# Circuito_Tappingduino_3_Final.net
KiCad netlist of a schematic drawn in EAGLE
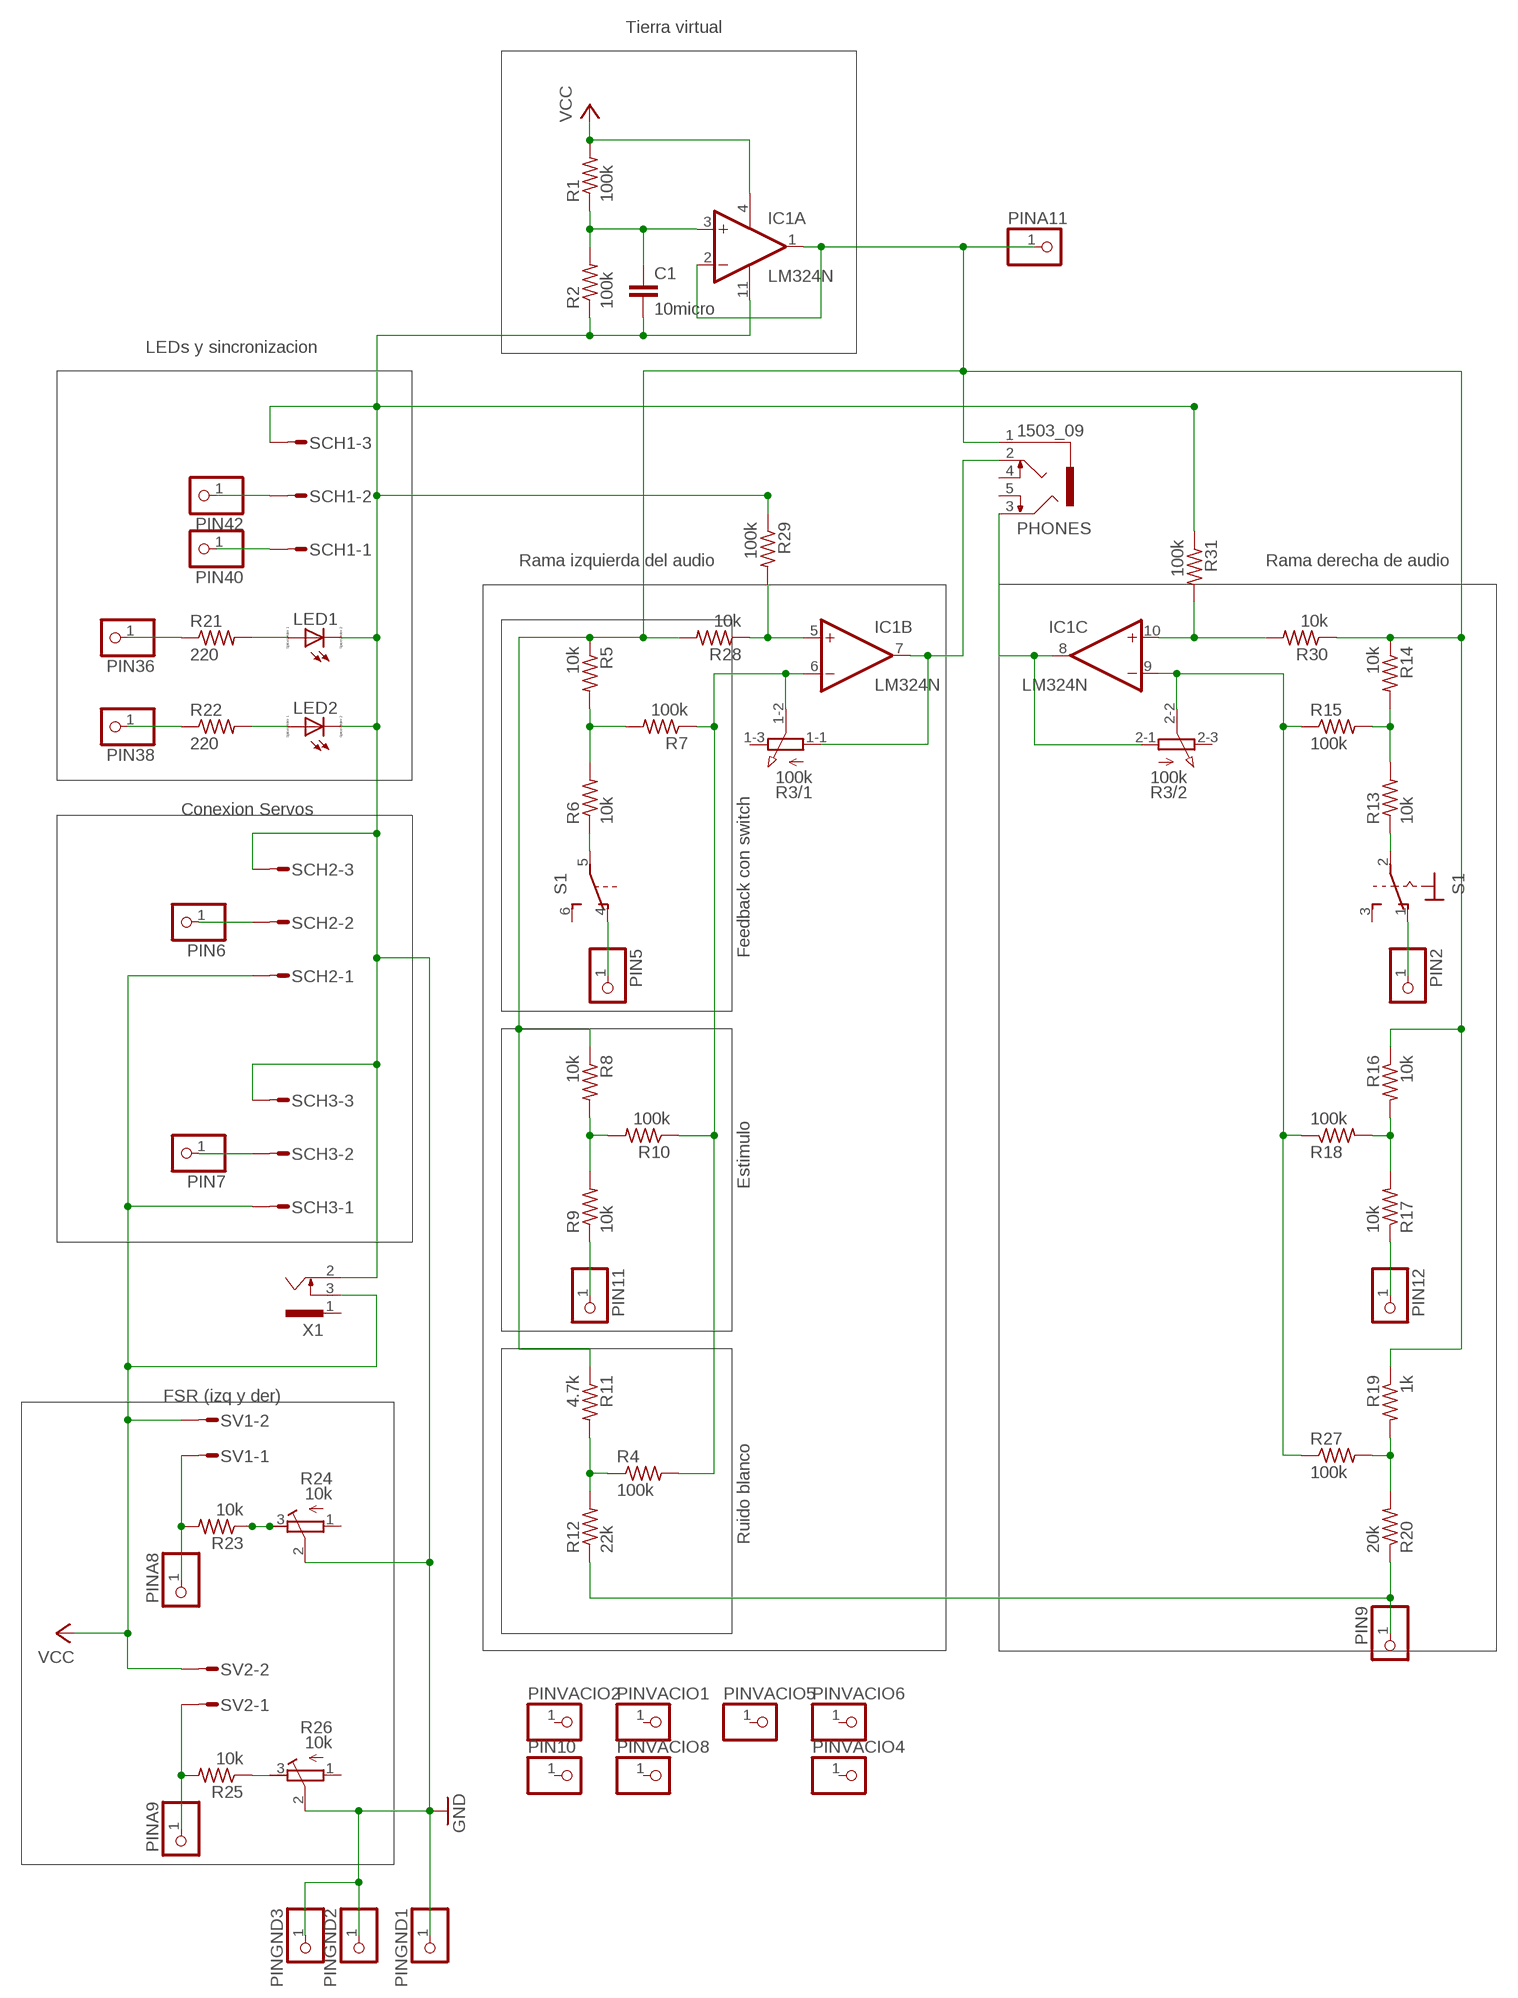
[diagram p0: schematic, sheet 1]

(export (version "E")
  (design (tool "Eeschema 10.0.6"))
  (components
    (comp (ref "C1")
      (value "10micro")
      (footprint "eagle-import:C025-030X050")
      (libsource (lib "eagle-import") (part "C-EU025-030X050"))
    )
    (comp (ref "IC1")
      (value "LM324N")
      (footprint "eagle-import:DIL14")
      (fields (field (name "SPICEPREFIX") "X"))
      (libsource (lib "eagle-import") (part "LM324N"))
    )
    (comp (ref "LED1")
      (value "LED_ELD260")
      (footprint "eagle-import:LED_LD260")
      (fields (field (name "SPICEMODEL") "DMOD"))
      (libsource (lib "eagle-import") (part "LED_ELD260"))
    )
    (comp (ref "LED2")
      (value "LED_ELD260")
      (footprint "eagle-import:LED_LD260")
      (fields (field (name "SPICEMODEL") "DMOD"))
      (libsource (lib "eagle-import") (part "LED_ELD260"))
    )
    (comp (ref "PHONES")
      (value "1503_09")
      (footprint "eagle-import:1503_09")
      (fields (field (name "SPICEPREFIX") "X"))
      (libsource (lib "eagle-import") (part "1503_09"))
    )
    (comp (ref "PIN2")
      (value "PINHD-1X1")
      (footprint "eagle-import:1X01")
      (fields (field (name "SPICEPREFIX") "X"))
      (libsource (lib "eagle-import") (part "PINHD-1X1"))
    )
    (comp (ref "PIN5")
      (value "PINHD-1X1")
      (footprint "eagle-import:1X01")
      (fields (field (name "SPICEPREFIX") "X"))
      (libsource (lib "eagle-import") (part "PINHD-1X1"))
    )
    (comp (ref "PIN6")
      (value "PINHD-1X1")
      (footprint "eagle-import:1X01")
      (fields (field (name "SPICEPREFIX") "X"))
      (libsource (lib "eagle-import") (part "PINHD-1X1"))
    )
    (comp (ref "PIN7")
      (value "PINHD-1X1")
      (footprint "eagle-import:1X01")
      (fields (field (name "SPICEPREFIX") "X"))
      (libsource (lib "eagle-import") (part "PINHD-1X1"))
    )
    (comp (ref "PIN9")
      (value "PINHD-1X1")
      (footprint "eagle-import:1X01")
      (fields (field (name "SPICEPREFIX") "X"))
      (libsource (lib "eagle-import") (part "PINHD-1X1"))
    )
    (comp (ref "PIN10")
      (value "PINHD-1X1")
      (footprint "eagle-import:1X01")
      (fields (field (name "SPICEPREFIX") "X"))
      (libsource (lib "eagle-import") (part "PINHD-1X1"))
    )
    (comp (ref "PIN11")
      (value "PINHD-1X1")
      (footprint "eagle-import:1X01")
      (fields (field (name "SPICEPREFIX") "X"))
      (libsource (lib "eagle-import") (part "PINHD-1X1"))
    )
    (comp (ref "PIN12")
      (value "PINHD-1X1")
      (footprint "eagle-import:1X01")
      (fields (field (name "SPICEPREFIX") "X"))
      (libsource (lib "eagle-import") (part "PINHD-1X1"))
    )
    (comp (ref "PIN36")
      (value "PINHD-1X1")
      (footprint "eagle-import:1X01")
      (fields (field (name "SPICEPREFIX") "X"))
      (libsource (lib "eagle-import") (part "PINHD-1X1"))
    )
    (comp (ref "PIN38")
      (value "PINHD-1X1")
      (footprint "eagle-import:1X01")
      (fields (field (name "SPICEPREFIX") "X"))
      (libsource (lib "eagle-import") (part "PINHD-1X1"))
    )
    (comp (ref "PIN40")
      (value "PINHD-1X1")
      (footprint "eagle-import:1X01")
      (fields (field (name "SPICEPREFIX") "X"))
      (libsource (lib "eagle-import") (part "PINHD-1X1"))
    )
    (comp (ref "PIN42")
      (value "PINHD-1X1")
      (footprint "eagle-import:1X01")
      (fields (field (name "SPICEPREFIX") "X"))
      (libsource (lib "eagle-import") (part "PINHD-1X1"))
    )
    (comp (ref "PINA8")
      (value "PINHD-1X1")
      (footprint "eagle-import:1X01")
      (fields (field (name "SPICEPREFIX") "X"))
      (libsource (lib "eagle-import") (part "PINHD-1X1"))
    )
    (comp (ref "PINA9")
      (value "PINHD-1X1")
      (footprint "eagle-import:1X01")
      (fields (field (name "SPICEPREFIX") "X"))
      (libsource (lib "eagle-import") (part "PINHD-1X1"))
    )
    (comp (ref "PINA11")
      (value "PINHD-1X1")
      (footprint "eagle-import:1X01")
      (fields (field (name "SPICEPREFIX") "X"))
      (libsource (lib "eagle-import") (part "PINHD-1X1"))
    )
    (comp (ref "PINGND1")
      (value "PINHD-1X1")
      (footprint "eagle-import:1X01")
      (fields (field (name "SPICEPREFIX") "X"))
      (libsource (lib "eagle-import") (part "PINHD-1X1"))
    )
    (comp (ref "PINGND2")
      (value "PINHD-1X1")
      (footprint "eagle-import:1X01")
      (fields (field (name "SPICEPREFIX") "X"))
      (libsource (lib "eagle-import") (part "PINHD-1X1"))
    )
    (comp (ref "PINGND3")
      (value "PINHD-1X1")
      (footprint "eagle-import:1X01")
      (fields (field (name "SPICEPREFIX") "X"))
      (libsource (lib "eagle-import") (part "PINHD-1X1"))
    )
    (comp (ref "PINVACIO1")
      (value "PINHD-1X1")
      (footprint "eagle-import:1X01")
      (fields (field (name "SPICEPREFIX") "X"))
      (libsource (lib "eagle-import") (part "PINHD-1X1"))
    )
    (comp (ref "PINVACIO2")
      (value "PINHD-1X1")
      (footprint "eagle-import:1X01")
      (fields (field (name "SPICEPREFIX") "X"))
      (libsource (lib "eagle-import") (part "PINHD-1X1"))
    )
    (comp (ref "PINVACIO4")
      (value "PINHD-1X1")
      (footprint "eagle-import:1X01")
      (fields (field (name "SPICEPREFIX") "X"))
      (libsource (lib "eagle-import") (part "PINHD-1X1"))
    )
    (comp (ref "PINVACIO5")
      (value "PINHD-1X1")
      (footprint "eagle-import:1X01")
      (fields (field (name "SPICEPREFIX") "X"))
      (libsource (lib "eagle-import") (part "PINHD-1X1"))
    )
    (comp (ref "PINVACIO6")
      (value "PINHD-1X1")
      (footprint "eagle-import:1X01")
      (fields (field (name "SPICEPREFIX") "X"))
      (libsource (lib "eagle-import") (part "PINHD-1X1"))
    )
    (comp (ref "PINVACIO8")
      (value "PINHD-1X1")
      (footprint "eagle-import:1X01")
      (fields (field (name "SPICEPREFIX") "X"))
      (libsource (lib "eagle-import") (part "PINHD-1X1"))
    )
    (comp (ref "R1")
      (value "100k")
      (footprint "eagle-import:0207_7")
      (libsource (lib "eagle-import") (part "R-US_0207/7"))
    )
    (comp (ref "R2")
      (value "100k")
      (footprint "eagle-import:0207_7")
      (libsource (lib "eagle-import") (part "R-US_0207/7"))
    )
    (comp (ref "R3")
      (value "100k")
      (footprint "eagle-import:3RP_1610G")
      (fields (field (name "SPICEPREFIX") "J"))
      (libsource (lib "eagle-import") (part "3RP/1610G"))
    )
    (comp (ref "R4")
      (value "100k")
      (footprint "eagle-import:0207_7")
      (libsource (lib "eagle-import") (part "R-US_0207/7"))
    )
    (comp (ref "R5")
      (value "10k")
      (footprint "eagle-import:0207_7")
      (libsource (lib "eagle-import") (part "R-US_0207/7"))
    )
    (comp (ref "R6")
      (value "10k")
      (footprint "eagle-import:0207_7")
      (libsource (lib "eagle-import") (part "R-US_0207/7"))
    )
    (comp (ref "R7")
      (value "100k")
      (footprint "eagle-import:0207_7")
      (libsource (lib "eagle-import") (part "R-US_0207/7"))
    )
    (comp (ref "R8")
      (value "10k")
      (footprint "eagle-import:0207_7")
      (libsource (lib "eagle-import") (part "R-US_0207/7"))
    )
    (comp (ref "R9")
      (value "10k")
      (footprint "eagle-import:0207_7")
      (libsource (lib "eagle-import") (part "R-US_0207/7"))
    )
    (comp (ref "R10")
      (value "100k")
      (footprint "eagle-import:0207_7")
      (libsource (lib "eagle-import") (part "R-US_0207/7"))
    )
    (comp (ref "R11")
      (value "4.7k")
      (footprint "eagle-import:0207_7")
      (libsource (lib "eagle-import") (part "R-US_0207/7"))
    )
    (comp (ref "R12")
      (value "22k")
      (footprint "eagle-import:0207_7")
      (libsource (lib "eagle-import") (part "R-US_0207/7"))
    )
    (comp (ref "R13")
      (value "10k")
      (footprint "eagle-import:0207_7")
      (libsource (lib "eagle-import") (part "R-US_0207/7"))
    )
    (comp (ref "R14")
      (value "10k")
      (footprint "eagle-import:0207_7")
      (libsource (lib "eagle-import") (part "R-US_0207/7"))
    )
    (comp (ref "R15")
      (value "100k")
      (footprint "eagle-import:0207_7")
      (libsource (lib "eagle-import") (part "R-US_0207/7"))
    )
    (comp (ref "R16")
      (value "10k")
      (footprint "eagle-import:0207_7")
      (libsource (lib "eagle-import") (part "R-US_0207/7"))
    )
    (comp (ref "R17")
      (value "10k")
      (footprint "eagle-import:0207_7")
      (libsource (lib "eagle-import") (part "R-US_0207/7"))
    )
    (comp (ref "R18")
      (value "100k")
      (footprint "eagle-import:0207_7")
      (libsource (lib "eagle-import") (part "R-US_0207/7"))
    )
    (comp (ref "R19")
      (value "1k")
      (footprint "eagle-import:0207_7")
      (libsource (lib "eagle-import") (part "R-US_0207/7"))
    )
    (comp (ref "R20")
      (value "20k")
      (footprint "eagle-import:0207_7")
      (libsource (lib "eagle-import") (part "R-US_0207/7"))
    )
    (comp (ref "R21")
      (value "220")
      (footprint "eagle-import:0207_7")
      (libsource (lib "eagle-import") (part "R-US_0207/7"))
    )
    (comp (ref "R22")
      (value "220")
      (footprint "eagle-import:0207_7")
      (libsource (lib "eagle-import") (part "R-US_0207/7"))
    )
    (comp (ref "R23")
      (value "10k")
      (footprint "eagle-import:0207_7")
      (libsource (lib "eagle-import") (part "R-US_0207/7"))
    )
    (comp (ref "R24")
      (value "10k")
      (footprint "eagle-import:RTRIM64W")
      (libsource (lib "eagle-import") (part "R-TRIMM64W"))
    )
    (comp (ref "R25")
      (value "10k")
      (footprint "eagle-import:0207_7")
      (libsource (lib "eagle-import") (part "R-US_0207/7"))
    )
    (comp (ref "R26")
      (value "10k")
      (footprint "eagle-import:RTRIM64W")
      (libsource (lib "eagle-import") (part "R-TRIMM64W"))
    )
    (comp (ref "R27")
      (value "100k")
      (footprint "eagle-import:0207_7")
      (libsource (lib "eagle-import") (part "R-US_0207/7"))
    )
    (comp (ref "R28")
      (value "10k")
      (footprint "eagle-import:0207_7")
      (libsource (lib "eagle-import") (part "R-US_0207/7"))
    )
    (comp (ref "R29")
      (value "100k")
      (footprint "eagle-import:0207_7")
      (libsource (lib "eagle-import") (part "R-US_0207/7"))
    )
    (comp (ref "R30")
      (value "10k")
      (footprint "eagle-import:0207_7")
      (libsource (lib "eagle-import") (part "R-US_0207/7"))
    )
    (comp (ref "R31")
      (value "100k")
      (footprint "eagle-import:0207_7")
      (libsource (lib "eagle-import") (part "R-US_0207/7"))
    )
    (comp (ref "S1")
      (value "320-938")
      (footprint "eagle-import:320-938")
      (libsource (lib "eagle-import") (part "320-938"))
    )
    (comp (ref "SCH1")
      (value "L03P")
      (footprint "eagle-import:L03P")
      (fields (field (name "SPICEPREFIX") "X"))
      (libsource (lib "eagle-import") (part "L03P"))
    )
    (comp (ref "SCH2")
      (value "L03P")
      (footprint "eagle-import:L03P")
      (fields (field (name "SPICEPREFIX") "X"))
      (libsource (lib "eagle-import") (part "L03P"))
    )
    (comp (ref "SCH3")
      (value "L03P")
      (footprint "eagle-import:L03P")
      (fields (field (name "SPICEPREFIX") "X"))
      (libsource (lib "eagle-import") (part "L03P"))
    )
    (comp (ref "SV1")
      (value "L02P")
      (footprint "eagle-import:L02P")
      (fields (field (name "SPICEPREFIX") "X"))
      (libsource (lib "eagle-import") (part "L02P"))
    )
    (comp (ref "SV2")
      (value "L02P")
      (footprint "eagle-import:L02P")
      (fields (field (name "SPICEPREFIX") "X"))
      (libsource (lib "eagle-import") (part "L02P"))
    )
    (comp (ref "X1")
      (value "SCD-014A")
      (footprint "eagle-import:SCD-014-A")
      (fields (field (name "SPICEPREFIX") "X"))
      (libsource (lib "eagle-import") (part "SCD-014A"))
    )
  )
  (nets
    (net (code "1") (name "GND") (class "Default")
      (node (ref "C1") (pin "2") (pinfunction "2_2") (pintype "passive"))
      (node (ref "IC1") (pin "11") (pinfunction "V-_11") (pintype "power_in"))
      (node (ref "LED1") (pin "K") (pinfunction "C_K") (pintype "passive"))
      (node (ref "LED2") (pin "K") (pinfunction "C_K") (pintype "passive"))
      (node (ref "PINGND1") (pin "1") (pinfunction "1_1") (pintype "passive"))
      (node (ref "PINGND2") (pin "1") (pinfunction "1_1") (pintype "passive"))
      (node (ref "PINGND3") (pin "1") (pinfunction "1_1") (pintype "passive"))
      (node (ref "R2") (pin "1") (pinfunction "1_1") (pintype "passive"))
      (node (ref "R24") (pin "2") (pinfunction "S_2") (pintype "passive"))
      (node (ref "R26") (pin "2") (pinfunction "S_2") (pintype "passive"))
      (node (ref "R29") (pin "1") (pinfunction "1_1") (pintype "passive"))
      (node (ref "R31") (pin "1") (pinfunction "1_1") (pintype "passive"))
      (node (ref "SCH1") (pin "3") (pinfunction "S_3") (pintype "passive"))
      (node (ref "SCH2") (pin "3") (pinfunction "S_3") (pintype "passive"))
      (node (ref "SCH3") (pin "3") (pinfunction "S_3") (pintype "passive"))
      (node (ref "X1") (pin "2") (pinfunction "2_2") (pintype "passive"))
    )
    (net (code "2") (name "Net-(IC1A-+IN)") (class "Default")
      (node (ref "C1") (pin "1") (pinfunction "1_1") (pintype "passive"))
      (node (ref "IC1") (pin "3") (pinfunction "+IN_3") (pintype "input"))
      (node (ref "R1") (pin "1") (pinfunction "1_1") (pintype "passive"))
      (node (ref "R2") (pin "2") (pinfunction "2_2") (pintype "passive"))
    )
    (net (code "3") (name "Net-(IC1A--IN)") (class "Default")
      (node (ref "IC1") (pin "1") (pinfunction "OUT_1") (pintype "output"))
      (node (ref "IC1") (pin "2") (pinfunction "-IN_2") (pintype "input"))
      (node (ref "PHONES") (pin "1") (pinfunction "1_1") (pintype "passive"))
      (node (ref "PINA11") (pin "1") (pinfunction "1_1") (pintype "passive"))
      (node (ref "R11") (pin "1") (pinfunction "1_1") (pintype "passive"))
      (node (ref "R14") (pin "1") (pinfunction "1_1") (pintype "passive"))
      (node (ref "R16") (pin "1") (pinfunction "1_1") (pintype "passive"))
      (node (ref "R19") (pin "1") (pinfunction "1_1") (pintype "passive"))
      (node (ref "R28") (pin "2") (pinfunction "2_2") (pintype "passive"))
      (node (ref "R30") (pin "1") (pinfunction "1_1") (pintype "passive"))
      (node (ref "R5") (pin "1") (pinfunction "1_1") (pintype "passive"))
      (node (ref "R8") (pin "1") (pinfunction "1_1") (pintype "passive"))
    )
    (net (code "4") (name "Net-(IC1B-+IN)") (class "Default")
      (node (ref "IC1") (pin "5") (pinfunction "+IN_5") (pintype "input"))
      (node (ref "R28") (pin "1") (pinfunction "1_1") (pintype "passive"))
      (node (ref "R29") (pin "2") (pinfunction "2_2") (pintype "passive"))
    )
    (net (code "5") (name "Net-(IC1B--IN)") (class "Default")
      (node (ref "IC1") (pin "6") (pinfunction "-IN_6") (pintype "input"))
      (node (ref "R10") (pin "1") (pinfunction "1_1") (pintype "passive"))
      (node (ref "R3") (pin "1-2") (pinfunction "S_1-2") (pintype "passive"))
      (node (ref "R4") (pin "2") (pinfunction "2_2") (pintype "passive"))
      (node (ref "R7") (pin "1") (pinfunction "1_1") (pintype "passive"))
    )
    (net (code "6") (name "Net-(IC1B-OUT)") (class "Default")
      (node (ref "IC1") (pin "7") (pinfunction "OUT_7") (pintype "output"))
      (node (ref "PHONES") (pin "2") (pinfunction "2_2") (pintype "passive"))
      (node (ref "R3") (pin "1-1") (pinfunction "A_1-1") (pintype "passive"))
    )
    (net (code "7") (name "Net-(IC1C-+IN)") (class "Default")
      (node (ref "IC1") (pin "10") (pinfunction "+IN_10") (pintype "input"))
      (node (ref "R30") (pin "2") (pinfunction "2_2") (pintype "passive"))
      (node (ref "R31") (pin "2") (pinfunction "2_2") (pintype "passive"))
    )
    (net (code "8") (name "Net-(IC1C--IN)") (class "Default")
      (node (ref "IC1") (pin "9") (pinfunction "-IN_9") (pintype "input"))
      (node (ref "R15") (pin "1") (pinfunction "1_1") (pintype "passive"))
      (node (ref "R18") (pin "1") (pinfunction "1_1") (pintype "passive"))
      (node (ref "R27") (pin "1") (pinfunction "1_1") (pintype "passive"))
      (node (ref "R3") (pin "2-2") (pinfunction "S_2-2") (pintype "passive"))
    )
    (net (code "9") (name "Net-(IC1C-OUT)") (class "Default")
      (node (ref "IC1") (pin "8") (pinfunction "OUT_8") (pintype "output"))
      (node (ref "PHONES") (pin "3") (pinfunction "3_3") (pintype "passive"))
      (node (ref "R3") (pin "2-1") (pinfunction "A_2-1") (pintype "passive"))
    )
    (net (code "10") (name "Net-(LED1-PadA)") (class "Default")
      (node (ref "LED1") (pin "A") (pinfunction "A_A") (pintype "passive"))
      (node (ref "R21") (pin "2") (pinfunction "2_2") (pintype "passive"))
    )
    (net (code "11") (name "Net-(LED2-PadA)") (class "Default")
      (node (ref "LED2") (pin "A") (pinfunction "A_A") (pintype "passive"))
      (node (ref "R22") (pin "2") (pinfunction "2_2") (pintype "passive"))
    )
    (net (code "12") (name "Net-(PIN9-Pad1)") (class "Default")
      (node (ref "PIN9") (pin "1") (pinfunction "1_1") (pintype "passive"))
      (node (ref "R12") (pin "1") (pinfunction "1_1") (pintype "passive"))
      (node (ref "R20") (pin "1") (pinfunction "1_1") (pintype "passive"))
    )
    (net (code "13") (name "Net-(PIN11-Pad1)") (class "Default")
      (node (ref "PIN11") (pin "1") (pinfunction "1_1") (pintype "passive"))
      (node (ref "R9") (pin "1") (pinfunction "1_1") (pintype "passive"))
    )
    (net (code "14") (name "Net-(PIN12-Pad1)") (class "Default")
      (node (ref "PIN12") (pin "1") (pinfunction "1_1") (pintype "passive"))
      (node (ref "R17") (pin "1") (pinfunction "1_1") (pintype "passive"))
    )
    (net (code "15") (name "Net-(PIN36-Pad1)") (class "Default")
      (node (ref "PIN36") (pin "1") (pinfunction "1_1") (pintype "passive"))
      (node (ref "R21") (pin "1") (pinfunction "1_1") (pintype "passive"))
    )
    (net (code "16") (name "Net-(PIN38-Pad1)") (class "Default")
      (node (ref "PIN38") (pin "1") (pinfunction "1_1") (pintype "passive"))
      (node (ref "R22") (pin "1") (pinfunction "1_1") (pintype "passive"))
    )
    (net (code "17") (name "Net-(R5-Pad2)") (class "Default")
      (node (ref "R5") (pin "2") (pinfunction "2_2") (pintype "passive"))
      (node (ref "R6") (pin "2") (pinfunction "2_2") (pintype "passive"))
      (node (ref "R7") (pin "2") (pinfunction "2_2") (pintype "passive"))
    )
    (net (code "18") (name "Net-(R10-Pad2)") (class "Default")
      (node (ref "R10") (pin "2") (pinfunction "2_2") (pintype "passive"))
      (node (ref "R8") (pin "2") (pinfunction "2_2") (pintype "passive"))
      (node (ref "R9") (pin "2") (pinfunction "2_2") (pintype "passive"))
    )
    (net (code "19") (name "Net-(R11-Pad2)") (class "Default")
      (node (ref "R11") (pin "2") (pinfunction "2_2") (pintype "passive"))
      (node (ref "R12") (pin "2") (pinfunction "2_2") (pintype "passive"))
      (node (ref "R4") (pin "1") (pinfunction "1_1") (pintype "passive"))
    )
    (net (code "20") (name "Net-(R13-Pad2)") (class "Default")
      (node (ref "R13") (pin "2") (pinfunction "2_2") (pintype "passive"))
      (node (ref "R14") (pin "2") (pinfunction "2_2") (pintype "passive"))
      (node (ref "R15") (pin "2") (pinfunction "2_2") (pintype "passive"))
    )
    (net (code "21") (name "Net-(R16-Pad2)") (class "Default")
      (node (ref "R16") (pin "2") (pinfunction "2_2") (pintype "passive"))
      (node (ref "R17") (pin "2") (pinfunction "2_2") (pintype "passive"))
      (node (ref "R18") (pin "2") (pinfunction "2_2") (pintype "passive"))
    )
    (net (code "22") (name "Net-(R19-Pad2)") (class "Default")
      (node (ref "R19") (pin "2") (pinfunction "2_2") (pintype "passive"))
      (node (ref "R20") (pin "2") (pinfunction "2_2") (pintype "passive"))
      (node (ref "R27") (pin "2") (pinfunction "2_2") (pintype "passive"))
    )
    (net (code "23") (name "Net-(R24-E)") (class "Default")
      (node (ref "R23") (pin "1") (pinfunction "1_1") (pintype "passive"))
      (node (ref "R24") (pin "3") (pinfunction "E_3") (pintype "passive"))
    )
    (net (code "24") (name "Net-(R26-E)") (class "Default")
      (node (ref "R25") (pin "1") (pinfunction "1_1") (pintype "passive"))
      (node (ref "R26") (pin "3") (pinfunction "E_3") (pintype "passive"))
    )
    (net (code "25") (name "Net-(S1A-O)") (class "Default")
      (node (ref "PIN2") (pin "1") (pinfunction "1_1") (pintype "passive"))
      (node (ref "S1") (pin "1") (pinfunction "O_1") (pintype "passive"))
    )
    (net (code "26") (name "Net-(S1A-P)") (class "Default")
      (node (ref "R13") (pin "1") (pinfunction "1_1") (pintype "passive"))
      (node (ref "S1") (pin "2") (pinfunction "P_2") (pintype "passive"))
    )
    (net (code "27") (name "Net-(S1B-O)") (class "Default")
      (node (ref "PIN5") (pin "1") (pinfunction "1_1") (pintype "passive"))
      (node (ref "S1") (pin "4") (pinfunction "O_4") (pintype "passive"))
    )
    (net (code "28") (name "Net-(S1B-P)") (class "Default")
      (node (ref "R6") (pin "1") (pinfunction "1_1") (pintype "passive"))
      (node (ref "S1") (pin "5") (pinfunction "P_5") (pintype "passive"))
    )
    (net (code "29") (name "Net-(SCH1A-S)") (class "Default")
      (node (ref "PIN40") (pin "1") (pinfunction "1_1") (pintype "passive"))
      (node (ref "SCH1") (pin "1") (pinfunction "S_1") (pintype "passive"))
    )
    (net (code "30") (name "Net-(SCH1B-S)") (class "Default")
      (node (ref "PIN42") (pin "1") (pinfunction "1_1") (pintype "passive"))
      (node (ref "SCH1") (pin "2") (pinfunction "S_2") (pintype "passive"))
    )
    (net (code "31") (name "Net-(SCH2B-S)") (class "Default")
      (node (ref "PIN6") (pin "1") (pinfunction "1_1") (pintype "passive"))
      (node (ref "SCH2") (pin "2") (pinfunction "S_2") (pintype "passive"))
    )
    (net (code "32") (name "Net-(SCH3B-S)") (class "Default")
      (node (ref "PIN7") (pin "1") (pinfunction "1_1") (pintype "passive"))
      (node (ref "SCH3") (pin "2") (pinfunction "S_2") (pintype "passive"))
    )
    (net (code "33") (name "Net-(SV1A-S)") (class "Default")
      (node (ref "PINA8") (pin "1") (pinfunction "1_1") (pintype "passive"))
      (node (ref "R23") (pin "2") (pinfunction "2_2") (pintype "passive"))
      (node (ref "SV1") (pin "1") (pinfunction "S_1") (pintype "passive"))
    )
    (net (code "34") (name "Net-(SV2A-S)") (class "Default")
      (node (ref "PINA9") (pin "1") (pinfunction "1_1") (pintype "passive"))
      (node (ref "R25") (pin "2") (pinfunction "2_2") (pintype "passive"))
      (node (ref "SV2") (pin "1") (pinfunction "S_1") (pintype "passive"))
    )
    (net (code "35") (name "VCC") (class "Default")
      (node (ref "IC1") (pin "4") (pinfunction "V+_4") (pintype "power_in"))
      (node (ref "R1") (pin "2") (pinfunction "2_2") (pintype "passive"))
      (node (ref "SCH2") (pin "1") (pinfunction "S_1") (pintype "passive"))
      (node (ref "SCH3") (pin "1") (pinfunction "S_1") (pintype "passive"))
      (node (ref "SV1") (pin "2") (pinfunction "S_2") (pintype "passive"))
      (node (ref "SV2") (pin "2") (pinfunction "S_2") (pintype "passive"))
      (node (ref "X1") (pin "3") (pinfunction "3_3") (pintype "passive"))
    )
    (net (code "36") (name "unconnected-(PHONES-Pad4)") (class "Default")
      (node (ref "PHONES") (pin "4") (pinfunction "4_4") (pintype "passive"))
    )
    (net (code "37") (name "unconnected-(PHONES-Pad5)") (class "Default")
      (node (ref "PHONES") (pin "5") (pinfunction "5_5") (pintype "passive"))
    )
    (net (code "38") (name "unconnected-(PIN10-Pad1)") (class "Default")
      (node (ref "PIN10") (pin "1") (pinfunction "1_1") (pintype "passive"))
    )
    (net (code "39") (name "unconnected-(PINVACIO1-Pad1)") (class "Default")
      (node (ref "PINVACIO1") (pin "1") (pinfunction "1_1") (pintype "passive"))
    )
    (net (code "40") (name "unconnected-(PINVACIO2-Pad1)") (class "Default")
      (node (ref "PINVACIO2") (pin "1") (pinfunction "1_1") (pintype "passive"))
    )
    (net (code "41") (name "unconnected-(PINVACIO4-Pad1)") (class "Default")
      (node (ref "PINVACIO4") (pin "1") (pinfunction "1_1") (pintype "passive"))
    )
    (net (code "42") (name "unconnected-(PINVACIO5-Pad1)") (class "Default")
      (node (ref "PINVACIO5") (pin "1") (pinfunction "1_1") (pintype "passive"))
    )
    (net (code "43") (name "unconnected-(PINVACIO6-Pad1)") (class "Default")
      (node (ref "PINVACIO6") (pin "1") (pinfunction "1_1") (pintype "passive"))
    )
    (net (code "44") (name "unconnected-(PINVACIO8-Pad1)") (class "Default")
      (node (ref "PINVACIO8") (pin "1") (pinfunction "1_1") (pintype "passive"))
    )
    (net (code "45") (name "unconnected-(R3A-E-Pad1-3)") (class "Default")
      (node (ref "R3") (pin "1-3") (pinfunction "E_1-3") (pintype "passive"))
    )
    (net (code "46") (name "unconnected-(R3B-E-Pad2-3)") (class "Default")
      (node (ref "R3") (pin "2-3") (pinfunction "E_2-3") (pintype "passive"))
    )
    (net (code "47") (name "unconnected-(R24-A-Pad1)") (class "Default")
      (node (ref "R24") (pin "1") (pinfunction "A_1") (pintype "passive"))
    )
    (net (code "48") (name "unconnected-(R26-A-Pad1)") (class "Default")
      (node (ref "R26") (pin "1") (pinfunction "A_1") (pintype "passive"))
    )
    (net (code "49") (name "unconnected-(S1A-S-Pad3)") (class "Default")
      (node (ref "S1") (pin "3") (pinfunction "S_3") (pintype "passive"))
    )
    (net (code "50") (name "unconnected-(S1B-S-Pad6)") (class "Default")
      (node (ref "S1") (pin "6") (pinfunction "S_6") (pintype "passive"))
    )
    (net (code "51") (name "unconnected-(X1-Pad1)") (class "Default")
      (node (ref "X1") (pin "1") (pinfunction "1_1") (pintype "passive"))
    )
  )
)
